# BoardPower.net
KiCad netlist of a schematic drawn in Altium Designer
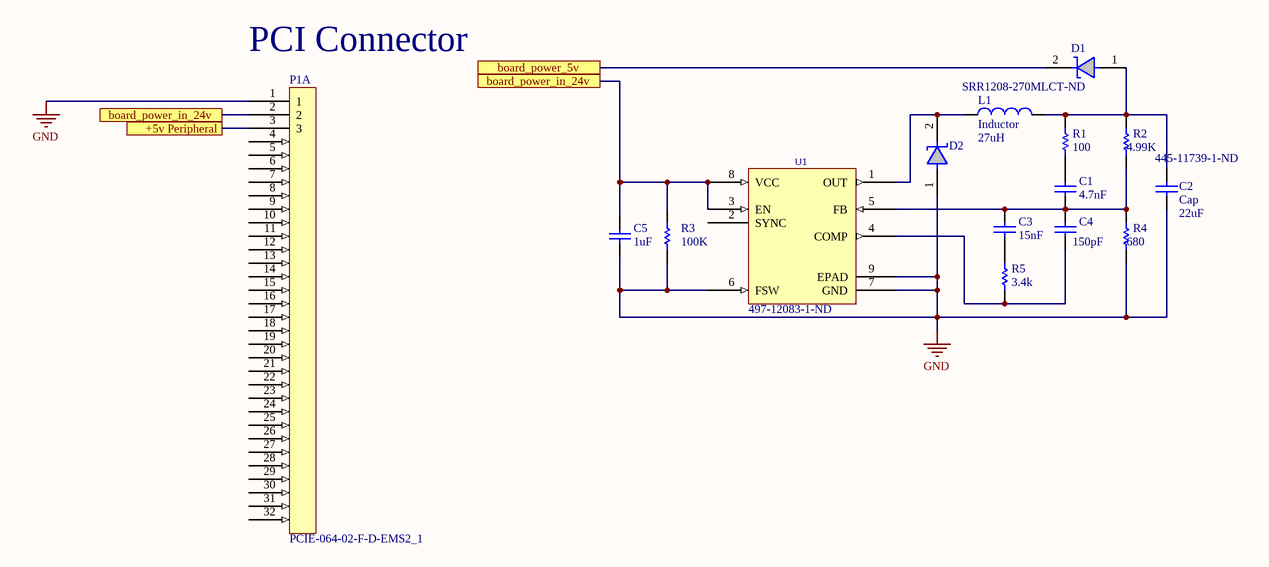
[diagram p0: BoardPower.SchDoc]

(export (version "E")
  (design (tool "Eeschema 10.0.6"))
  (components
    (comp (ref "C1")
      (value "4.7nF")
      (footprint "0603")
      (description "4.7nF 10% 50V")
      (fields (field (name "TOLERANCE") "10%") (field (name "VOLTAGE") "50V"))
      (libsource (lib "CPHComponentSource") (part "CAP_2"))
    )
    (comp (ref "C2")
      (value "Cap")
      (footprint "C1206")
      (description "Capacitor")
      (fields
        (field (name "ALTIUM_VALUE") "22uF")
        (field (name "SUPPLIER PART NUMBER 1") "445-11739-1-ND")
        (field (name "MANUFACTURER") "TDK")
        (field (name "MANUFACTURER PART NUMBER") "C3216JB1V226M160AC")
        (field (name "PUBLISHER") "Altium Limited")
      )
      (libsource (lib "Miscellaneous Devices") (part "Cap"))
    )
    (comp (ref "C3")
      (value "15nF")
      (footprint "0603")
      (description "15nF 10% 50V")
      (fields (field (name "TOLERANCE") "10%") (field (name "VOLTAGE") "50V"))
      (libsource (lib "CPHComponentSource") (part "CAP_1_17"))
    )
    (comp (ref "C4")
      (value "150pF")
      (footprint "0402")
      (description "150pF 5% 50V")
      (fields
        (field (name "MANUFACTURER") "AVX Corporation")
        (field (name "MANUFACTURER PART NUMBER") "04025A151JAT2A")
      )
      (libsource (lib "CPHComponentSource") (part "CAP_1_16"))
    )
    (comp (ref "C5")
      (value "1uF")
      (footprint "0402")
      (description "1uF 10% 50V")
      (fields
        (field (name "MANUFACTURER") "Samsung Electro-Mechanics")
        (field (name "MANUFACTURER PART NUMBER") "CL05A105KA5NQNC")
      )
      (libsource (lib "CPHComponentSource") (part "CAP_1_21_3"))
    )
    (comp (ref "D1")
      (value "SCHOTTKY DIODE")
      (footprint "SOT-23")
      (fields (field (name "MANUFACTURER") "Diodes") (field (name "MANUFACTURER PART NUMBER") "BAT54-7-F"))
      (libsource (lib "") (part "SCHOTTKY DIODE_1"))
    )
    (comp (ref "D2")
      (value "SCHOTTKY DIODE")
      (footprint "SOT-23")
      (fields (field (name "MANUFACTURER") "Diodes") (field (name "MANUFACTURER PART NUMBER") "BAT54-7-F"))
      (libsource (lib "CPHComponentSource") (part "SCHOTTKY DIODE"))
    )
    (comp (ref "L1")
      (value "Inductor")
      (footprint "IND_BOURNS_SRR12")
      (description "FIXED IND 27UH 3A 48 MOHM SMD")
      (fields
        (field (name "ALTIUM_VALUE") "27uH")
        (field (name "SUPPLIER PART NUMBER 1") "SRR1208-270MLCT-ND")
        (field (name "MANUFACTURER") "Bourns")
        (field (name "MANUFACTURER PART NUMBER") "SRR1208-270ML")
        (field (name "PUBLISHER") "Altium Limited")
      )
      (libsource (lib "Miscellaneous Devices") (part "Inductor"))
    )
    (comp (ref "P1")
      (value "PCIE-064-02-F-D-EMS2_1")
      (footprint "PCIE-064-02-F-D-EMS2")
      (libsource (lib "PCIE-064-02-F-D-EMS2") (part "PCIE-064-02-F-D-EMS2_1"))
    )
    (comp (ref "R1")
      (value "100")
      (footprint "0603")
      (description "RES 100 0.1W ±1% 0603 (1608)")
      (fields
        (field (name "MANUFACTURER") "Panasonic Electronic Components")
        (field (name "MANUFACTURER PART NUMBER") "ERA-3AEB101V")
      )
      (libsource (lib "CPHComponentSource") (part "RES_9"))
    )
    (comp (ref "R2")
      (value "4.99K")
      (footprint "0402")
      (description "RES 4.99K ±1% 0603 (1608)")
      (fields
        (field (name "MANUFACTURER") "Panasonic Electronic Components")
        (field (name "MANUFACTURER PART NUMBER") "ERA-2AEB4991X")
      )
      (libsource (lib "CPHComponentSource") (part "RES_38"))
    )
    (comp (ref "R3")
      (value "100K")
      (footprint "0402")
      (description "RES 100K 0.1W ±1% 0603 (1608 Metric)")
      (fields
        (field (name "MANUFACTURER") "Vishay Dale")
        (field (name "MANUFACTURER PART NUMBER") "TNPW0402100KBEED")
      )
      (libsource (lib "CPHComponentSource") (part "RES_11"))
    )
    (comp (ref "R4")
      (value "680")
      (footprint "0402")
      (description "RES 680 ±1% 0603 (1608)")
      (fields
        (field (name "MANUFACTURER") "Panasonic Electronic Components")
        (field (name "MANUFACTURER PART NUMBER") "ERA-2AED681X")
      )
      (libsource (lib "CPHComponentSource") (part "RES_49"))
    )
    (comp (ref "R5")
      (value "3.4k")
      (footprint "0603")
      (description "RES 3.4K ±1% 0603 (1608)")
      (fields
        (field (name "MANUFACTURER") "Panasonic")
        (field (name "MANUFACTURER PART NUMBER") "ERA3AEB3401V")
      )
      (libsource (lib "CPHComponentSource") (part "RES_32"))
    )
    (comp (ref "U1")
      (value "L7986ATR")
      (footprint "L7986ATR")
      (description "IC Switching Regulator 3A STEP-DOWN 8-HSOP")
      (fields (field (name "SUPPLIER PART NUMBER 1") "497-12083-1-ND"))
      (libsource (lib "CPHComponentSource") (part "L7986ATR"))
    )
  )
  (nets
    (net (code "1") (name "/+5v Peripheral") (class "Default")
      (node (ref "P1") (pin "3") (pinfunction "3_3") (pintype "power_in"))
    )
    (net (code "2") (name "/board_power_5v") (class "Default")
      (node (ref "D1") (pin "2") (pinfunction "K_2") (pintype "passive"))
    )
    (net (code "3") (name "/board_power_in_24v") (class "Default")
      (node (ref "C5") (pin "2") (pinfunction "2_2") (pintype "passive"))
      (node (ref "P1") (pin "2") (pinfunction "2_2") (pintype "power_in"))
      (node (ref "R3") (pin "1") (pinfunction "1_1") (pintype "passive"))
      (node (ref "U1") (pin "3") (pinfunction "EN_3") (pintype "input"))
      (node (ref "U1") (pin "8") (pinfunction "VCC_8") (pintype "input"))
    )
    (net (code "4") (name "GND") (class "Default")
      (node (ref "C2") (pin "1") (pinfunction "1_1") (pintype "passive"))
      (node (ref "C5") (pin "1") (pinfunction "1_1") (pintype "passive"))
      (node (ref "D2") (pin "1") (pinfunction "A_1") (pintype "passive"))
      (node (ref "P1") (pin "1") (pinfunction "1_1") (pintype "power_in"))
      (node (ref "R3") (pin "2") (pinfunction "2_2") (pintype "passive"))
      (node (ref "R4") (pin "1") (pinfunction "1_1") (pintype "passive"))
      (node (ref "U1") (pin "6") (pinfunction "FSW_6") (pintype "input"))
      (node (ref "U1") (pin "7") (pinfunction "GND_7") (pintype "power_in"))
      (node (ref "U1") (pin "9") (pinfunction "EPAD_9") (pintype "power_in"))
    )
    (net (code "5") (name "Net-(C1-Pad1)") (class "Default")
      (node (ref "C1") (pin "1") (pinfunction "1_1") (pintype "passive"))
      (node (ref "R1") (pin "1") (pinfunction "1_1") (pintype "passive"))
    )
    (net (code "6") (name "Net-(C3-Pad1)") (class "Default")
      (node (ref "C3") (pin "1") (pinfunction "1_1") (pintype "passive"))
      (node (ref "R5") (pin "2") (pinfunction "2_2") (pintype "passive"))
    )
    (net (code "7") (name "Net-(D1-A)") (class "Default")
      (node (ref "C2") (pin "2") (pinfunction "2_2") (pintype "passive"))
      (node (ref "D1") (pin "1") (pinfunction "A_1") (pintype "passive"))
      (node (ref "L1") (pin "2") (pinfunction "2_2") (pintype "passive"))
      (node (ref "R1") (pin "2") (pinfunction "2_2") (pintype "passive"))
      (node (ref "R2") (pin "2") (pinfunction "2_2") (pintype "passive"))
    )
    (net (code "8") (name "Net-(D2-K)") (class "Default")
      (node (ref "D2") (pin "2") (pinfunction "K_2") (pintype "passive"))
      (node (ref "L1") (pin "1") (pinfunction "1_1") (pintype "passive"))
      (node (ref "U1") (pin "1") (pinfunction "OUT_1") (pintype "output"))
    )
    (net (code "9") (name "Net-(U1-COMP)") (class "Default")
      (node (ref "C4") (pin "1") (pinfunction "1_1") (pintype "passive"))
      (node (ref "R5") (pin "1") (pinfunction "1_1") (pintype "passive"))
      (node (ref "U1") (pin "4") (pinfunction "COMP_4") (pintype "output"))
    )
    (net (code "10") (name "Net-(U1-FB)") (class "Default")
      (node (ref "C1") (pin "2") (pinfunction "2_2") (pintype "passive"))
      (node (ref "C3") (pin "2") (pinfunction "2_2") (pintype "passive"))
      (node (ref "C4") (pin "2") (pinfunction "2_2") (pintype "passive"))
      (node (ref "R2") (pin "1") (pinfunction "1_1") (pintype "passive"))
      (node (ref "R4") (pin "2") (pinfunction "2_2") (pintype "passive"))
      (node (ref "U1") (pin "5") (pinfunction "FB_5") (pintype "input"))
    )
    (net (code "11") (name "unconnected-(P1-Pad4)") (class "Default")
      (node (ref "P1") (pin "4") (pintype "input"))
    )
    (net (code "12") (name "unconnected-(P1-Pad5)") (class "Default")
      (node (ref "P1") (pin "5") (pintype "input"))
    )
    (net (code "13") (name "unconnected-(P1-Pad6)") (class "Default")
      (node (ref "P1") (pin "6") (pintype "input"))
    )
    (net (code "14") (name "unconnected-(P1-Pad7)") (class "Default")
      (node (ref "P1") (pin "7") (pintype "input"))
    )
    (net (code "15") (name "unconnected-(P1-Pad8)") (class "Default")
      (node (ref "P1") (pin "8") (pintype "input"))
    )
    (net (code "16") (name "unconnected-(P1-Pad9)") (class "Default")
      (node (ref "P1") (pin "9") (pintype "input"))
    )
    (net (code "17") (name "unconnected-(P1-Pad10)") (class "Default")
      (node (ref "P1") (pin "10") (pintype "input"))
    )
    (net (code "18") (name "unconnected-(P1-Pad11)") (class "Default")
      (node (ref "P1") (pin "11") (pintype "input"))
    )
    (net (code "19") (name "unconnected-(P1-Pad12)") (class "Default")
      (node (ref "P1") (pin "12") (pintype "input"))
    )
    (net (code "20") (name "unconnected-(P1-Pad13)") (class "Default")
      (node (ref "P1") (pin "13") (pintype "input"))
    )
    (net (code "21") (name "unconnected-(P1-Pad14)") (class "Default")
      (node (ref "P1") (pin "14") (pintype "input"))
    )
    (net (code "22") (name "unconnected-(P1-Pad15)") (class "Default")
      (node (ref "P1") (pin "15") (pintype "input"))
    )
    (net (code "23") (name "unconnected-(P1-Pad16)") (class "Default")
      (node (ref "P1") (pin "16") (pintype "input"))
    )
    (net (code "24") (name "unconnected-(P1-Pad17)") (class "Default")
      (node (ref "P1") (pin "17") (pintype "input"))
    )
    (net (code "25") (name "unconnected-(P1-Pad18)") (class "Default")
      (node (ref "P1") (pin "18") (pintype "input"))
    )
    (net (code "26") (name "unconnected-(P1-Pad19)") (class "Default")
      (node (ref "P1") (pin "19") (pintype "input"))
    )
    (net (code "27") (name "unconnected-(P1-Pad20)") (class "Default")
      (node (ref "P1") (pin "20") (pintype "input"))
    )
    (net (code "28") (name "unconnected-(P1-Pad21)") (class "Default")
      (node (ref "P1") (pin "21") (pintype "input"))
    )
    (net (code "29") (name "unconnected-(P1-Pad22)") (class "Default")
      (node (ref "P1") (pin "22") (pintype "input"))
    )
    (net (code "30") (name "unconnected-(P1-Pad23)") (class "Default")
      (node (ref "P1") (pin "23") (pintype "input"))
    )
    (net (code "31") (name "unconnected-(P1-Pad24)") (class "Default")
      (node (ref "P1") (pin "24") (pintype "input"))
    )
    (net (code "32") (name "unconnected-(P1-Pad25)") (class "Default")
      (node (ref "P1") (pin "25") (pintype "input"))
    )
    (net (code "33") (name "unconnected-(P1-Pad26)") (class "Default")
      (node (ref "P1") (pin "26") (pintype "input"))
    )
    (net (code "34") (name "unconnected-(P1-Pad27)") (class "Default")
      (node (ref "P1") (pin "27") (pintype "input"))
    )
    (net (code "35") (name "unconnected-(P1-Pad28)") (class "Default")
      (node (ref "P1") (pin "28") (pintype "input"))
    )
    (net (code "36") (name "unconnected-(P1-Pad29)") (class "Default")
      (node (ref "P1") (pin "29") (pintype "input"))
    )
    (net (code "37") (name "unconnected-(P1-Pad30)") (class "Default")
      (node (ref "P1") (pin "30") (pintype "input"))
    )
    (net (code "38") (name "unconnected-(P1-Pad31)") (class "Default")
      (node (ref "P1") (pin "31") (pintype "input"))
    )
    (net (code "39") (name "unconnected-(P1-Pad32)") (class "Default")
      (node (ref "P1") (pin "32") (pintype "input"))
    )
    (net (code "40") (name "unconnected-(U1-SYNC-Pad2)") (class "Default")
      (node (ref "U1") (pin "2") (pinfunction "SYNC_2") (pintype "passive"))
    )
  )
)
